# XephConnect_v0_6.net
KiCad netlist of a schematic drawn in EAGLE
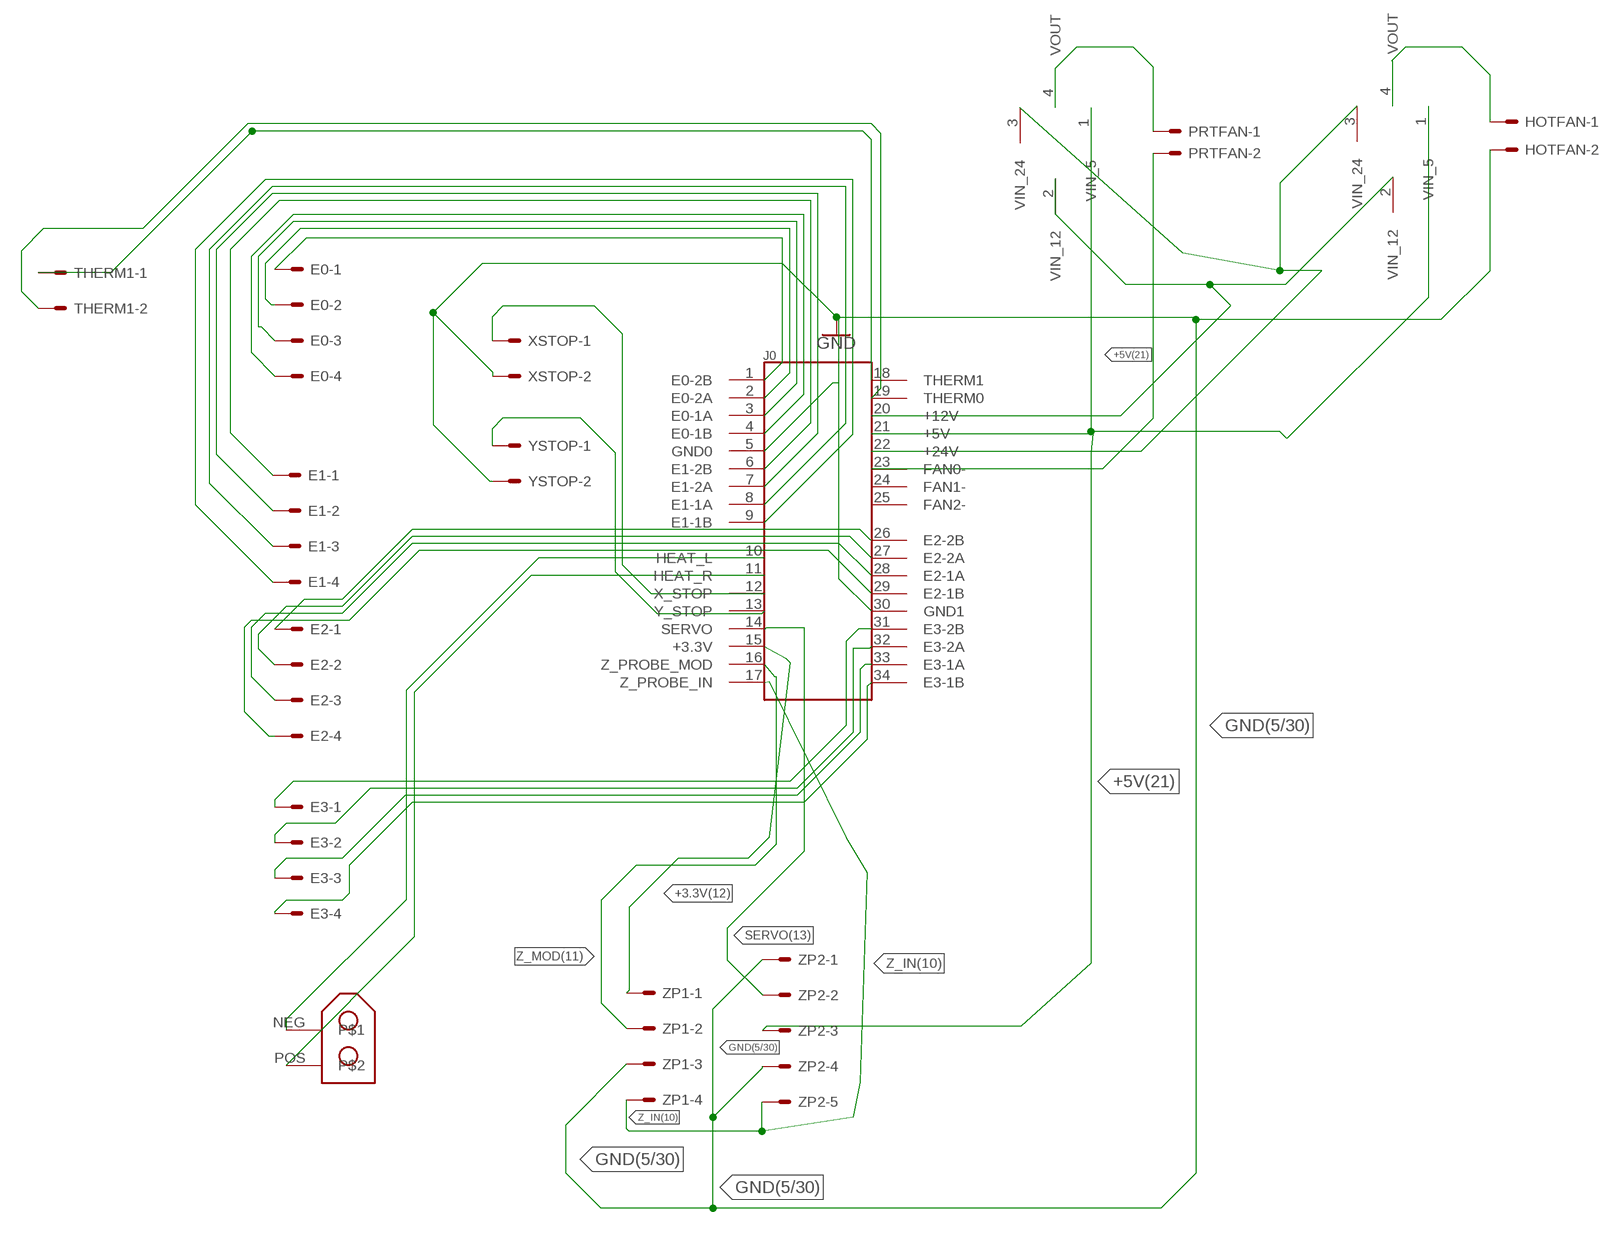
[diagram p0: schematic, sheet 1]

(export (version "E")
  (design (tool "Eeschema 10.0.6"))
  (components
    (comp (ref "E0")
      (value "22-27-2041-04")
      (footprint "eagle-import:6410-04")
      (fields (field (name "MF") "MOLEX"))
      (libsource (lib "eagle-import") (part "22-?-0427-2041"))
    )
    (comp (ref "E1")
      (value "22-27-2041-04")
      (footprint "eagle-import:6410-04")
      (fields (field (name "MF") "MOLEX"))
      (libsource (lib "eagle-import") (part "22-?-0427-2041"))
    )
    (comp (ref "E2")
      (value "22-27-2041-04")
      (footprint "eagle-import:6410-04")
      (fields (field (name "MF") "MOLEX"))
      (libsource (lib "eagle-import") (part "22-?-0427-2041"))
    )
    (comp (ref "E3")
      (value "22-27-2041-04")
      (footprint "eagle-import:6410-04")
      (fields (field (name "MF") "MOLEX"))
      (libsource (lib "eagle-import") (part "22-?-0427-2041"))
    )
    (comp (ref "HOTFAN")
      (value "22-27-2021-02")
      (footprint "eagle-import:6410-02")
      (fields (field (name "MF") "MOLEX"))
      (libsource (lib "eagle-import") (part "22-?-0227-2021"))
    )
    (comp (ref "J0")
      (value "6437288-1-V2")
      (footprint "eagle-import:TE_6437288-1")
      (libsource (lib "eagle-import") (part "6437288-1-V2"))
    )
    (comp (ref "PRTFAN")
      (value "22-27-2021-02")
      (footprint "eagle-import:6410-02")
      (fields (field (name "MF") "MOLEX"))
      (libsource (lib "eagle-import") (part "22-?-0227-2021"))
    )
    (comp (ref "THERM1")
      (value "22-27-2021-02")
      (footprint "eagle-import:6410-02")
      (fields (field (name "MF") "MOLEX"))
      (libsource (lib "eagle-import") (part "22-?-0227-2021"))
    )
    (comp (ref "U$1")
      (value "CONN_03+01(T)(SM)")
      (footprint "eagle-import:1X03X01(SM)")
      (libsource (lib "eagle-import") (part "CONN_03+01(T)(SM)"))
    )
    (comp (ref "U$2")
      (value "CONN_03+01(T)(SM)")
      (footprint "eagle-import:1X03X01(SM)")
      (libsource (lib "eagle-import") (part "CONN_03+01(T)(SM)"))
    )
    (comp (ref "U$3")
      (value "XT30")
      (footprint "eagle-import:XT30-90")
      (libsource (lib "eagle-import") (part "XT30"))
    )
    (comp (ref "XSTOP")
      (value "22-27-2021-02")
      (footprint "eagle-import:6410-02")
      (fields (field (name "MF") "MOLEX"))
      (libsource (lib "eagle-import") (part "22-?-0227-2021"))
    )
    (comp (ref "YSTOP")
      (value "22-27-2021-02")
      (footprint "eagle-import:6410-02")
      (fields (field (name "MF") "MOLEX"))
      (libsource (lib "eagle-import") (part "22-?-0227-2021"))
    )
    (comp (ref "ZP1")
      (value "22-27-2041-04")
      (footprint "eagle-import:6410-04")
      (fields (field (name "MF") "MOLEX"))
      (libsource (lib "eagle-import") (part "22-?-0427-2041"))
    )
    (comp (ref "ZP2")
      (value "22-27-2051-05")
      (footprint "eagle-import:6410-05")
      (fields (field (name "MF") "MOLEX"))
      (libsource (lib "eagle-import") (part "22-?-0527-2051"))
    )
  )
  (nets
    (net (code "1") (name "+3.3V(12)") (class "Default")
      (node (ref "J0") (pin "15") (pinfunction "+3.3V_15") (pintype "power_in"))
      (node (ref "ZP1") (pin "1") (pinfunction "S_1") (pintype "passive"))
    )
    (net (code "2") (name "+5V(21)") (class "Default")
      (node (ref "J0") (pin "21") (pinfunction "+5V_21") (pintype "power_in"))
      (node (ref "U$1") (pin "1") (pinfunction "VIN_5_1") (pintype "power_in"))
      (node (ref "U$2") (pin "1") (pinfunction "VIN_5_1") (pintype "power_in"))
      (node (ref "ZP2") (pin "3") (pinfunction "S_3") (pintype "passive"))
    )
    (net (code "3") (name "/FAN1-") (class "Default")
      (node (ref "J0") (pin "24") (pinfunction "FAN1-_24") (pintype "power_in"))
    )
    (net (code "4") (name "/FAN2-") (class "Default")
      (node (ref "J0") (pin "25") (pinfunction "FAN2-_25") (pintype "power_in"))
    )
    (net (code "5") (name "GND(5{slash}30)") (class "Default")
      (node (ref "HOTFAN") (pin "2") (pinfunction "S_2") (pintype "passive"))
      (node (ref "J0") (pin "30") (pinfunction "GND1_30") (pintype "power_in"))
      (node (ref "J0") (pin "5") (pinfunction "GND0_5") (pintype "power_in"))
      (node (ref "XSTOP") (pin "2") (pinfunction "S_2") (pintype "passive"))
      (node (ref "YSTOP") (pin "2") (pinfunction "S_2") (pintype "passive"))
      (node (ref "ZP1") (pin "3") (pinfunction "S_3") (pintype "passive"))
      (node (ref "ZP2") (pin "1") (pinfunction "S_1") (pintype "passive"))
      (node (ref "ZP2") (pin "4") (pinfunction "S_4") (pintype "passive"))
    )
    (net (code "6") (name "Net-(E0A-S)") (class "Default")
      (node (ref "E0") (pin "1") (pinfunction "S_1") (pintype "passive"))
      (node (ref "J0") (pin "1") (pinfunction "E0-2B_1") (pintype "bidirectional"))
    )
    (net (code "7") (name "Net-(E0B-S)") (class "Default")
      (node (ref "E0") (pin "2") (pinfunction "S_2") (pintype "passive"))
      (node (ref "J0") (pin "2") (pinfunction "E0-2A_2") (pintype "bidirectional"))
    )
    (net (code "8") (name "Net-(E0C-S)") (class "Default")
      (node (ref "E0") (pin "3") (pinfunction "S_3") (pintype "passive"))
      (node (ref "J0") (pin "3") (pinfunction "E0-1A_3") (pintype "bidirectional"))
    )
    (net (code "9") (name "Net-(E0D-S)") (class "Default")
      (node (ref "E0") (pin "4") (pinfunction "S_4") (pintype "passive"))
      (node (ref "J0") (pin "4") (pinfunction "E0-1B_4") (pintype "bidirectional"))
    )
    (net (code "10") (name "Net-(E1A-S)") (class "Default")
      (node (ref "E1") (pin "1") (pinfunction "S_1") (pintype "passive"))
      (node (ref "J0") (pin "6") (pinfunction "E1-2B_6") (pintype "bidirectional"))
    )
    (net (code "11") (name "Net-(E1B-S)") (class "Default")
      (node (ref "E1") (pin "2") (pinfunction "S_2") (pintype "passive"))
      (node (ref "J0") (pin "7") (pinfunction "E1-2A_7") (pintype "bidirectional"))
    )
    (net (code "12") (name "Net-(E1C-S)") (class "Default")
      (node (ref "E1") (pin "3") (pinfunction "S_3") (pintype "passive"))
      (node (ref "J0") (pin "8") (pinfunction "E1-1A_8") (pintype "bidirectional"))
    )
    (net (code "13") (name "Net-(E1D-S)") (class "Default")
      (node (ref "E1") (pin "4") (pinfunction "S_4") (pintype "passive"))
      (node (ref "J0") (pin "9") (pinfunction "E1-1B_9") (pintype "bidirectional"))
    )
    (net (code "14") (name "Net-(E2A-S)") (class "Default")
      (node (ref "E2") (pin "1") (pinfunction "S_1") (pintype "passive"))
      (node (ref "J0") (pin "26") (pinfunction "E2-2B_26") (pintype "bidirectional"))
    )
    (net (code "15") (name "Net-(E2B-S)") (class "Default")
      (node (ref "E2") (pin "2") (pinfunction "S_2") (pintype "passive"))
      (node (ref "J0") (pin "27") (pinfunction "E2-2A_27") (pintype "bidirectional"))
    )
    (net (code "16") (name "Net-(E2C-S)") (class "Default")
      (node (ref "E2") (pin "3") (pinfunction "S_3") (pintype "passive"))
      (node (ref "J0") (pin "28") (pinfunction "E2-1A_28") (pintype "bidirectional"))
    )
    (net (code "17") (name "Net-(E2D-S)") (class "Default")
      (node (ref "E2") (pin "4") (pinfunction "S_4") (pintype "passive"))
      (node (ref "J0") (pin "29") (pinfunction "E2-1B_29") (pintype "bidirectional"))
    )
    (net (code "18") (name "Net-(E3A-S)") (class "Default")
      (node (ref "E3") (pin "1") (pinfunction "S_1") (pintype "passive"))
      (node (ref "J0") (pin "31") (pinfunction "E3-2B_31") (pintype "bidirectional"))
    )
    (net (code "19") (name "Net-(E3B-S)") (class "Default")
      (node (ref "E3") (pin "2") (pinfunction "S_2") (pintype "passive"))
      (node (ref "J0") (pin "32") (pinfunction "E3-2A_32") (pintype "bidirectional"))
    )
    (net (code "20") (name "Net-(E3C-S)") (class "Default")
      (node (ref "E3") (pin "3") (pinfunction "S_3") (pintype "passive"))
      (node (ref "J0") (pin "33") (pinfunction "E3-1A_33") (pintype "bidirectional"))
    )
    (net (code "21") (name "Net-(E3D-S)") (class "Default")
      (node (ref "E3") (pin "4") (pinfunction "S_4") (pintype "passive"))
      (node (ref "J0") (pin "34") (pinfunction "E3-1B_34") (pintype "bidirectional"))
    )
    (net (code "22") (name "Net-(HOTFANA-S)") (class "Default")
      (node (ref "HOTFAN") (pin "1") (pinfunction "S_1") (pintype "passive"))
      (node (ref "U$2") (pin "4") (pinfunction "VOUT_4") (pintype "power_in"))
    )
    (net (code "23") (name "Net-(J0-+12V)") (class "Default")
      (node (ref "J0") (pin "20") (pinfunction "+12V_20") (pintype "power_in"))
      (node (ref "U$1") (pin "2") (pinfunction "VIN_12_2") (pintype "power_in"))
      (node (ref "U$2") (pin "2") (pinfunction "VIN_12_2") (pintype "power_in"))
    )
    (net (code "24") (name "Net-(J0-+24V)") (class "Default")
      (node (ref "J0") (pin "22") (pinfunction "+24V_22") (pintype "power_in"))
      (node (ref "U$1") (pin "3") (pinfunction "VIN_24_3") (pintype "power_in"))
      (node (ref "U$2") (pin "3") (pinfunction "VIN_24_3") (pintype "power_in"))
    )
    (net (code "25") (name "Net-(J0-FAN0-)") (class "Default")
      (node (ref "J0") (pin "23") (pinfunction "FAN0-_23") (pintype "power_in"))
      (node (ref "PRTFAN") (pin "2") (pinfunction "S_2") (pintype "passive"))
    )
    (net (code "26") (name "Net-(J0-HEAT_L)") (class "Default")
      (node (ref "J0") (pin "10") (pinfunction "HEAT_L_10") (pintype "power_in"))
      (node (ref "U$3") (pin "NEG") (pinfunction "P$1_NEG") (pintype "bidirectional"))
    )
    (net (code "27") (name "Net-(J0-HEAT_R)") (class "Default")
      (node (ref "J0") (pin "11") (pinfunction "HEAT_R_11") (pintype "power_in"))
      (node (ref "U$3") (pin "POS") (pinfunction "P$2_POS") (pintype "bidirectional"))
    )
    (net (code "28") (name "Net-(J0-THERM0)") (class "Default")
      (node (ref "J0") (pin "19") (pinfunction "THERM0_19") (pintype "power_in"))
      (node (ref "THERM1") (pin "2") (pinfunction "S_2") (pintype "passive"))
    )
    (net (code "29") (name "Net-(J0-THERM1)") (class "Default")
      (node (ref "J0") (pin "18") (pinfunction "THERM1_18") (pintype "power_in"))
      (node (ref "THERM1") (pin "1") (pinfunction "S_1") (pintype "passive"))
    )
    (net (code "30") (name "Net-(J0-X_STOP)") (class "Default")
      (node (ref "J0") (pin "12") (pinfunction "X_STOP_12") (pintype "bidirectional"))
      (node (ref "XSTOP") (pin "1") (pinfunction "S_1") (pintype "passive"))
    )
    (net (code "31") (name "Net-(J0-Y_STOP)") (class "Default")
      (node (ref "J0") (pin "13") (pinfunction "Y_STOP_13") (pintype "bidirectional"))
      (node (ref "YSTOP") (pin "1") (pinfunction "S_1") (pintype "passive"))
    )
    (net (code "32") (name "Net-(PRTFANA-S)") (class "Default")
      (node (ref "PRTFAN") (pin "1") (pinfunction "S_1") (pintype "passive"))
      (node (ref "U$1") (pin "4") (pinfunction "VOUT_4") (pintype "power_in"))
    )
    (net (code "33") (name "SERVO(13)") (class "Default")
      (node (ref "J0") (pin "14") (pinfunction "SERVO_14") (pintype "bidirectional"))
      (node (ref "ZP2") (pin "2") (pinfunction "S_2") (pintype "passive"))
    )
    (net (code "34") (name "Z_IN(10)") (class "Default")
      (node (ref "J0") (pin "17") (pinfunction "Z_PROBE_IN_17") (pintype "bidirectional"))
      (node (ref "ZP1") (pin "4") (pinfunction "S_4") (pintype "passive"))
      (node (ref "ZP2") (pin "5") (pinfunction "S_5") (pintype "passive"))
    )
    (net (code "35") (name "Z_MOD(11)") (class "Default")
      (node (ref "J0") (pin "16") (pinfunction "Z_PROBE_MOD_16") (pintype "bidirectional"))
      (node (ref "ZP1") (pin "2") (pinfunction "S_2") (pintype "passive"))
    )
  )
)
